# Smart_Extruder_Board.net
KiCad netlist of a schematic drawn in EAGLE
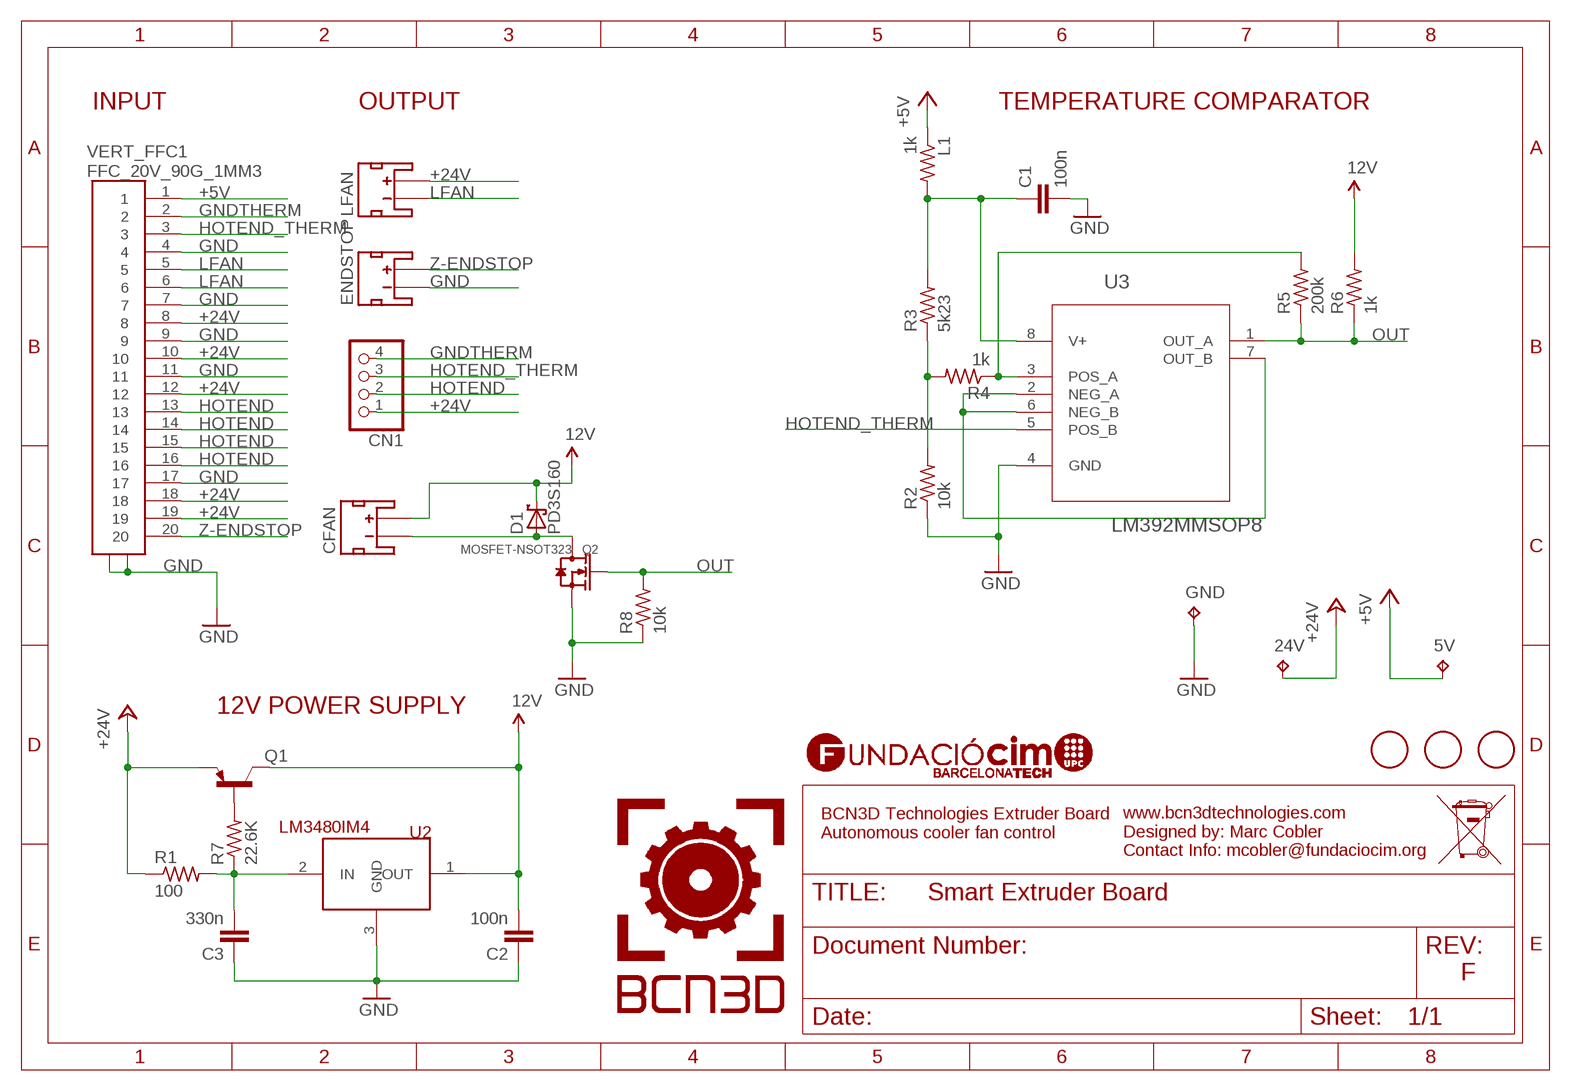
[diagram p0: schematic, sheet 1]

(export (version "E")
  (design (tool "Eeschema 10.0.6"))
  (components
    (comp (ref "5V")
      (value "TPB1,27")
      (footprint "eagle-import:B1,27")
      (libsource (lib "eagle-import") (part "TPB1,27"))
    )
    (comp (ref "24V")
      (value "TPB1,27")
      (footprint "eagle-import:B1,27")
      (libsource (lib "eagle-import") (part "TPB1,27"))
    )
    (comp (ref "C1")
      (value "100n")
      (footprint "eagle-import:C0603K")
      (fields (field (name "MF") "AVX") (field (name "MPN") "06035C104KAT2A"))
      (libsource (lib "eagle-import") (part "C-EUC0603K"))
    )
    (comp (ref "C2")
      (value "100n")
      (footprint "eagle-import:C0603K")
      (fields (field (name "MF") "AVX") (field (name "MPN") "06035C104KAT2A"))
      (libsource (lib "eagle-import") (part "C-EUC0603K"))
    )
    (comp (ref "C3")
      (value "330n")
      (footprint "eagle-import:C0805")
      (fields (field (name "MF") "MURATA") (field (name "MPN") "GRM219R71H334KA88D"))
      (libsource (lib "eagle-import") (part "C-EUC0805"))
    )
    (comp (ref "CFAN")
      (value "JST_2MM_MALE")
      (footprint "eagle-import:JST-2-SMD")
      (fields
        (field (name "MF") "JST (JAPAN SOLDERLESS TERMINALS)")
        (field (name "MPN") "S2B-PH-SM4-TB(LF)(SN)")
      )
      (libsource (lib "eagle-import") (part "JST_2MM_MALE"))
    )
    (comp (ref "CN1")
      (value "JST_4PINPA")
      (footprint "eagle-import:JST_PA_04")
      (fields
        (field (name "MF") "JST (JAPAN SOLDERLESS TERMINALS)")
        (field (name "MPN") "SM04B-PASS-TBT(LF)(SN)")
      )
      (libsource (lib "eagle-import") (part "JST_4PINPA"))
    )
    (comp (ref "D1")
      (value "PD3S160")
      (footprint "eagle-import:POWERDI323")
      (fields (field (name "MF") "DIODES INC.") (field (name "MPN") "PD3S160-7"))
      (libsource (lib "eagle-import") (part "PD3S160"))
    )
    (comp (ref "ENDSTOP")
      (value "JST_2MM_MALE")
      (footprint "eagle-import:JST-2-SMD")
      (fields
        (field (name "MF") "JST (JAPAN SOLDERLESS TERMINALS)")
        (field (name "MPN") "S2B-PH-SM4-TB(LF)(SN)")
      )
      (libsource (lib "eagle-import") (part "JST_2MM_MALE"))
    )
    (comp (ref "GND")
      (value "TPB1,27")
      (footprint "eagle-import:B1,27")
      (libsource (lib "eagle-import") (part "TPB1,27"))
    )
    (comp (ref "L1")
      (value "1k")
      (footprint "eagle-import:R0603")
      (fields (field (name "MF") "MULTICOMP") (field (name "MPN") "MCMR06X1001FTL"))
      (libsource (lib "eagle-import") (part "R-US_R0603"))
    )
    (comp (ref "LFAN")
      (value "JST_2MM_MALE")
      (footprint "eagle-import:JST-2-SMD")
      (fields
        (field (name "MF") "JST (JAPAN SOLDERLESS TERMINALS)")
        (field (name "MPN") "S2B-PH-SM4-TB(LF)(SN)")
      )
      (libsource (lib "eagle-import") (part "JST_2MM_MALE"))
    )
    (comp (ref "Q1")
      (value "BC807W")
      (footprint "eagle-import:SOT323-BEC")
      (fields (field (name "MF") "NXP") (field (name "MPN") "BC807W,115"))
      (libsource (lib "eagle-import") (part "BC807W"))
    )
    (comp (ref "Q2")
      (value "MOSFET-NSOT323")
      (footprint "eagle-import:SOT323")
      (fields (field (name "MF") "NXP") (field (name "MPN") "PMF370XN,115"))
      (libsource (lib "eagle-import") (part "MOSFET-NSOT323"))
    )
    (comp (ref "R1")
      (value "100")
      (footprint "eagle-import:R1210")
      (fields (field (name "MF") "MULTICOMP") (field (name "MPN") "MC0603SAF330JT5E"))
      (libsource (lib "eagle-import") (part "R-US_R1210"))
    )
    (comp (ref "R2")
      (value "10k")
      (footprint "eagle-import:R0603")
      (fields (field (name "MF") "MULTICOMP") (field (name "MPN") "MCMR06X1002FTL"))
      (libsource (lib "eagle-import") (part "R-US_R0603"))
    )
    (comp (ref "R3")
      (value "5k23")
      (footprint "eagle-import:R0603")
      (fields (field (name "MF") "PANASONIC ELECTRONIC COMPONENTS") (field (name "MPN") "ERJ3EKF5231V"))
      (libsource (lib "eagle-import") (part "R-US_R0603"))
    )
    (comp (ref "R4")
      (value "1k")
      (footprint "eagle-import:R0603")
      (fields (field (name "MF") "MULTICOMP") (field (name "MPN") "MCMR06X1001FTL"))
      (libsource (lib "eagle-import") (part "R-US_R0603"))
    )
    (comp (ref "R5")
      (value "200k")
      (footprint "eagle-import:R0603")
      (fields (field (name "MF") "PANASONIC ELECTRONIC COMPONENTS") (field (name "MPN") "ERJ3EKF2003V"))
      (libsource (lib "eagle-import") (part "R-US_R0603"))
    )
    (comp (ref "R6")
      (value "1k")
      (footprint "eagle-import:R0603")
      (fields (field (name "MF") "MULTICOMP") (field (name "MPN") "MCMR06X1001FTL"))
      (libsource (lib "eagle-import") (part "R-US_R0603"))
    )
    (comp (ref "R7")
      (value "22.6K")
      (footprint "eagle-import:R0603")
      (fields (field (name "MF") "MULTICOMP") (field (name "MPN") "MC0603SAF330JT5E"))
      (libsource (lib "eagle-import") (part "R-US_R0603"))
    )
    (comp (ref "R8")
      (value "10k")
      (footprint "eagle-import:R0603")
      (fields (field (name "MF") "MULTICOMP") (field (name "MPN") "MCMR06X1002FTL"))
      (libsource (lib "eagle-import") (part "R-US_R0603"))
    )
    (comp (ref "U$1")
      (value "FIDUCIAL")
      (footprint "eagle-import:FIDUCIAL_1MM")
      (libsource (lib "eagle-import") (part "FIDUCIAL"))
    )
    (comp (ref "U$2")
      (value "FIDUCIAL")
      (footprint "eagle-import:FIDUCIAL_1MM")
      (libsource (lib "eagle-import") (part "FIDUCIAL"))
    )
    (comp (ref "U$3")
      (value "FIDUCIAL")
      (footprint "eagle-import:FIDUCIAL_1MM")
      (libsource (lib "eagle-import") (part "FIDUCIAL"))
    )
    (comp (ref "U2")
      (value "LM3480IM4")
      (footprint "eagle-import:SOT23-3")
      (fields (field (name "MF") "TEXAS INSTRUMENTS") (field (name "MPN") "LM3480IM3-12/NOPB"))
      (libsource (lib "eagle-import") (part "LM3480IM4"))
    )
    (comp (ref "U3")
      (value "LM392MMSOP8")
      (footprint "eagle-import:MSOP8")
      (libsource (lib "eagle-import") (part "LM392MMSOP8"))
    )
    (comp (ref "VERT_FFC1")
      (value "FFC_20V_90G_1MM3")
      (footprint "eagle-import:FCI_20WAY_1MM_3ST")
      (libsource (lib "eagle-import") (part "FFC_20V_90G_1MM3"))
    )
  )
  (nets
    (net (code "1") (name "+5V") (class "Default")
      (node (ref "5V") (pin "TP") (pinfunction "TP_TP") (pintype "input"))
      (node (ref "L1") (pin "1") (pinfunction "1_1") (pintype "passive"))
      (node (ref "VERT_FFC1") (pin "1") (pinfunction "1_1") (pintype "bidirectional"))
    )
    (net (code "2") (name "+24V") (class "Default")
      (node (ref "24V") (pin "TP") (pinfunction "TP_TP") (pintype "input"))
      (node (ref "CN1") (pin "1") (pinfunction "1_1") (pintype "passive"))
      (node (ref "LFAN") (pin "2") (pinfunction "+_2") (pintype "bidirectional"))
      (node (ref "Q1") (pin "2") (pinfunction "E_2") (pintype "passive"))
      (node (ref "R1") (pin "1") (pinfunction "1_1") (pintype "passive"))
      (node (ref "VERT_FFC1") (pin "10") (pinfunction "10_10") (pintype "bidirectional"))
      (node (ref "VERT_FFC1") (pin "12") (pinfunction "12_12") (pintype "bidirectional"))
      (node (ref "VERT_FFC1") (pin "18") (pinfunction "18_18") (pintype "bidirectional"))
      (node (ref "VERT_FFC1") (pin "19") (pinfunction "19_19") (pintype "bidirectional"))
      (node (ref "VERT_FFC1") (pin "8") (pinfunction "8_8") (pintype "bidirectional"))
    )
    (net (code "3") (name "/GNDTHERM") (class "Default")
      (node (ref "CN1") (pin "4") (pinfunction "4_4") (pintype "passive"))
      (node (ref "VERT_FFC1") (pin "2") (pinfunction "2_2") (pintype "bidirectional"))
    )
    (net (code "4") (name "/HOTEND") (class "Default")
      (node (ref "CN1") (pin "2") (pinfunction "2_2") (pintype "passive"))
      (node (ref "VERT_FFC1") (pin "13") (pinfunction "13_13") (pintype "bidirectional"))
      (node (ref "VERT_FFC1") (pin "14") (pinfunction "14_14") (pintype "bidirectional"))
      (node (ref "VERT_FFC1") (pin "15") (pinfunction "15_15") (pintype "bidirectional"))
      (node (ref "VERT_FFC1") (pin "16") (pinfunction "16_16") (pintype "bidirectional"))
    )
    (net (code "5") (name "/HOTEND_THERM") (class "Default")
      (node (ref "CN1") (pin "3") (pinfunction "3_3") (pintype "passive"))
      (node (ref "U3") (pin "5") (pinfunction "POS_B_5") (pintype "input"))
      (node (ref "VERT_FFC1") (pin "3") (pinfunction "3_3") (pintype "bidirectional"))
    )
    (net (code "6") (name "/LFAN") (class "Default")
      (node (ref "LFAN") (pin "1") (pinfunction "-_1") (pintype "bidirectional"))
      (node (ref "VERT_FFC1") (pin "5") (pinfunction "5_5") (pintype "bidirectional"))
      (node (ref "VERT_FFC1") (pin "6") (pinfunction "6_6") (pintype "bidirectional"))
    )
    (net (code "7") (name "/OUT") (class "Default")
      (node (ref "Q2") (pin "1") (pinfunction "G_1") (pintype "passive"))
      (node (ref "R5") (pin "1") (pinfunction "1_1") (pintype "passive"))
      (node (ref "R6") (pin "1") (pinfunction "1_1") (pintype "passive"))
      (node (ref "R8") (pin "2") (pinfunction "2_2") (pintype "passive"))
      (node (ref "U3") (pin "1") (pinfunction "OUT_A_1") (pintype "output"))
    )
    (net (code "8") (name "/Z-ENDSTOP") (class "Default")
      (node (ref "ENDSTOP") (pin "2") (pinfunction "+_2") (pintype "bidirectional"))
      (node (ref "VERT_FFC1") (pin "20") (pinfunction "20_20") (pintype "bidirectional"))
    )
    (net (code "9") (name "12V") (class "Default")
      (node (ref "C2") (pin "2") (pinfunction "2_2") (pintype "passive"))
      (node (ref "CFAN") (pin "2") (pinfunction "+_2") (pintype "bidirectional"))
      (node (ref "D1") (pin "C") (pinfunction "C_C") (pintype "passive"))
      (node (ref "Q1") (pin "3") (pinfunction "C_3") (pintype "passive"))
      (node (ref "R6") (pin "2") (pinfunction "2_2") (pintype "passive"))
      (node (ref "U2") (pin "1") (pinfunction "OUT_1") (pintype "bidirectional"))
    )
    (net (code "10") (name "GND") (class "Default")
      (node (ref "C1") (pin "2") (pinfunction "2_2") (pintype "passive"))
      (node (ref "C2") (pin "1") (pinfunction "1_1") (pintype "passive"))
      (node (ref "C3") (pin "1") (pinfunction "1_1") (pintype "passive"))
      (node (ref "ENDSTOP") (pin "1") (pinfunction "-_1") (pintype "bidirectional"))
      (node (ref "GND") (pin "TP") (pinfunction "TP_TP") (pintype "input"))
      (node (ref "Q2") (pin "2") (pinfunction "S_2") (pintype "passive"))
      (node (ref "R2") (pin "1") (pinfunction "1_1") (pintype "passive"))
      (node (ref "R8") (pin "1") (pinfunction "1_1") (pintype "passive"))
      (node (ref "U2") (pin "3") (pinfunction "GND_3") (pintype "bidirectional"))
      (node (ref "U3") (pin "4") (pinfunction "GND_4") (pintype "passive"))
      (node (ref "VERT_FFC1") (pin "11") (pinfunction "11_11") (pintype "bidirectional"))
      (node (ref "VERT_FFC1") (pin "17") (pinfunction "17_17") (pintype "bidirectional"))
      (node (ref "VERT_FFC1") (pin "4") (pinfunction "4_4") (pintype "bidirectional"))
      (node (ref "VERT_FFC1") (pin "7") (pinfunction "7_7") (pintype "bidirectional"))
      (node (ref "VERT_FFC1") (pin "9") (pinfunction "9_9") (pintype "bidirectional"))
      (node (ref "VERT_FFC1") (pin "GND1") (pinfunction "GND_GND1") (pintype "bidirectional"))
      (node (ref "VERT_FFC1") (pin "GND2") (pinfunction "GND_GND2") (pintype "bidirectional"))
    )
    (net (code "11") (name "Net-(CFAN--)") (class "Default")
      (node (ref "CFAN") (pin "1") (pinfunction "-_1") (pintype "bidirectional"))
      (node (ref "D1") (pin "A") (pinfunction "A_A") (pintype "passive"))
      (node (ref "Q2") (pin "3") (pinfunction "D_3") (pintype "passive"))
    )
    (net (code "12") (name "Net-(Q1-B)") (class "Default")
      (node (ref "Q1") (pin "1") (pinfunction "B_1") (pintype "passive"))
      (node (ref "R7") (pin "2") (pinfunction "2_2") (pintype "passive"))
    )
    (net (code "13") (name "Net-(R2-Pad2)") (class "Default")
      (node (ref "R2") (pin "2") (pinfunction "2_2") (pintype "passive"))
      (node (ref "R3") (pin "1") (pinfunction "1_1") (pintype "passive"))
      (node (ref "R4") (pin "2") (pinfunction "2_2") (pintype "passive"))
    )
    (net (code "14") (name "Net-(U2-IN)") (class "Default")
      (node (ref "C3") (pin "2") (pinfunction "2_2") (pintype "passive"))
      (node (ref "R1") (pin "2") (pinfunction "2_2") (pintype "passive"))
      (node (ref "R7") (pin "1") (pinfunction "1_1") (pintype "passive"))
      (node (ref "U2") (pin "2") (pinfunction "IN_2") (pintype "bidirectional"))
    )
    (net (code "15") (name "Net-(U3-NEG_A)") (class "Default")
      (node (ref "U3") (pin "2") (pinfunction "NEG_A_2") (pintype "input"))
      (node (ref "U3") (pin "6") (pinfunction "NEG_B_6") (pintype "input"))
      (node (ref "U3") (pin "7") (pinfunction "OUT_B_7") (pintype "output"))
    )
    (net (code "16") (name "Net-(U3-POS_A)") (class "Default")
      (node (ref "R4") (pin "1") (pinfunction "1_1") (pintype "passive"))
      (node (ref "R5") (pin "2") (pinfunction "2_2") (pintype "passive"))
      (node (ref "U3") (pin "3") (pinfunction "POS_A_3") (pintype "input"))
    )
    (net (code "17") (name "Net-(U3-V+)") (class "Default")
      (node (ref "C1") (pin "1") (pinfunction "1_1") (pintype "passive"))
      (node (ref "L1") (pin "2") (pinfunction "2_2") (pintype "passive"))
      (node (ref "R3") (pin "2") (pinfunction "2_2") (pintype "passive"))
      (node (ref "U3") (pin "8") (pinfunction "V+_8") (pintype "power_in"))
    )
    (net (code "18") (name "unconnected-(CFAN-PAD1-PadNC1)") (class "Default")
      (node (ref "CFAN") (pin "NC1") (pinfunction "PAD1_NC1") (pintype "bidirectional"))
    )
    (net (code "19") (name "unconnected-(CFAN-PAD2-PadNC2)") (class "Default")
      (node (ref "CFAN") (pin "NC2") (pinfunction "PAD2_NC2") (pintype "bidirectional"))
    )
    (net (code "20") (name "unconnected-(ENDSTOP-PAD1-PadNC1)") (class "Default")
      (node (ref "ENDSTOP") (pin "NC1") (pinfunction "PAD1_NC1") (pintype "bidirectional"))
    )
    (net (code "21") (name "unconnected-(ENDSTOP-PAD2-PadNC2)") (class "Default")
      (node (ref "ENDSTOP") (pin "NC2") (pinfunction "PAD2_NC2") (pintype "bidirectional"))
    )
    (net (code "22") (name "unconnected-(LFAN-PAD1-PadNC1)") (class "Default")
      (node (ref "LFAN") (pin "NC1") (pinfunction "PAD1_NC1") (pintype "bidirectional"))
    )
    (net (code "23") (name "unconnected-(LFAN-PAD2-PadNC2)") (class "Default")
      (node (ref "LFAN") (pin "NC2") (pinfunction "PAD2_NC2") (pintype "bidirectional"))
    )
  )
)
